# main.net
KiCad netlist of a schematic drawn in Altium Designer
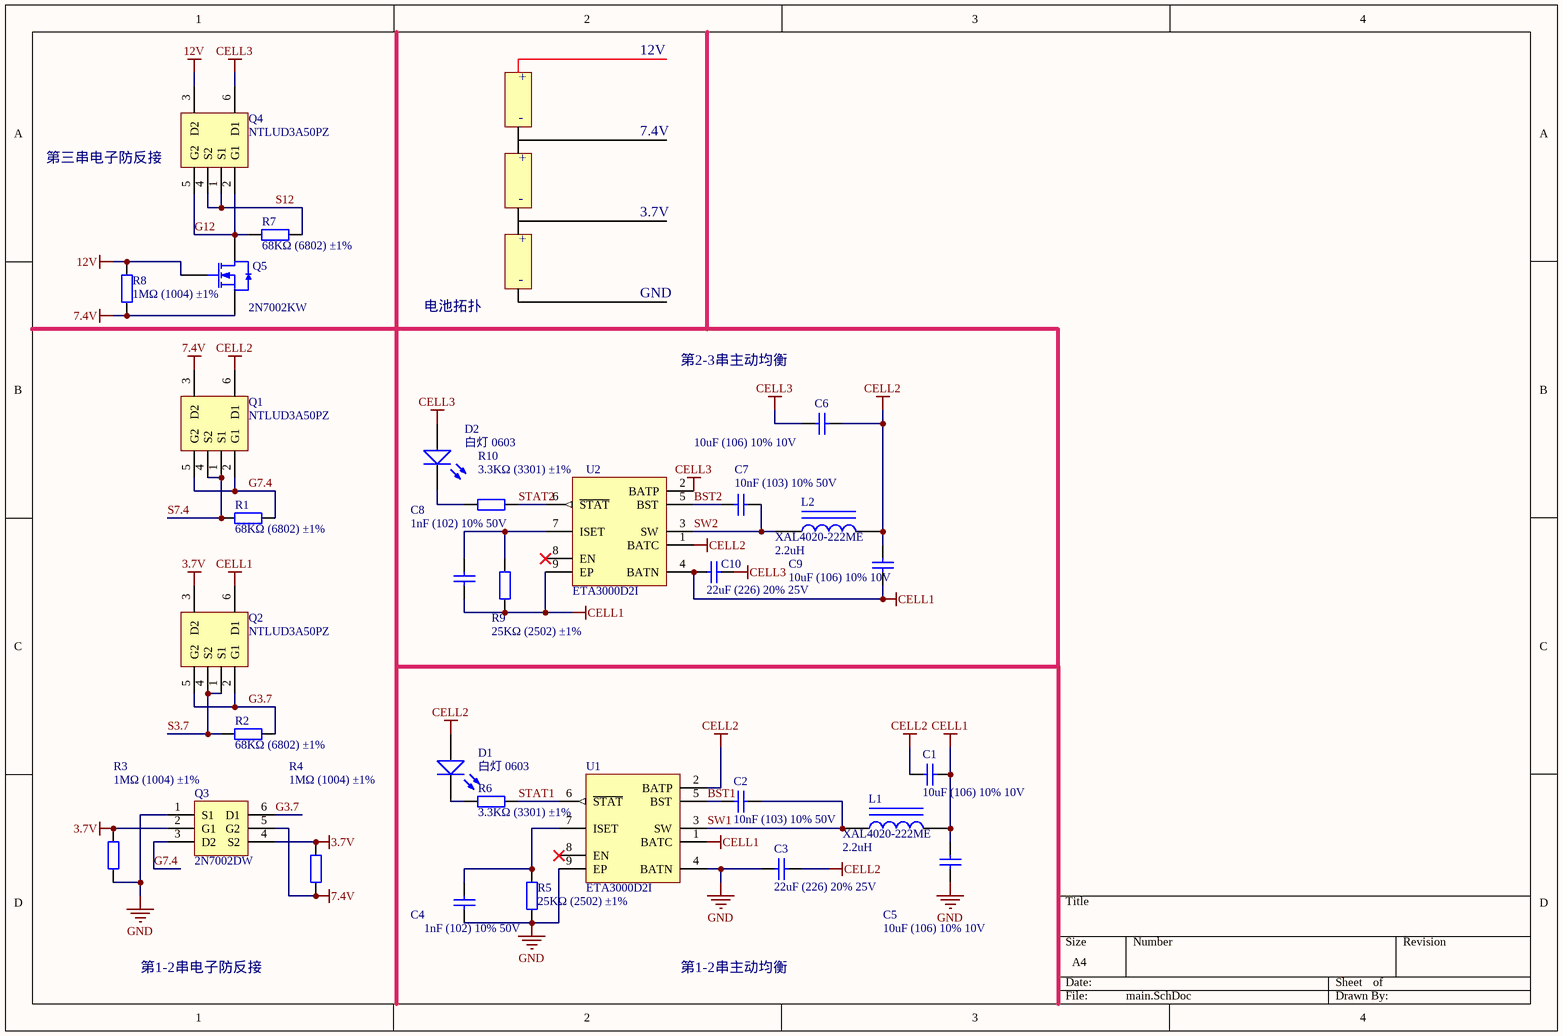
[diagram p0: main.SchDoc]

(export (version "E")
  (design (tool "Eeschema 10.0.6"))
  (components
    (comp (ref "C1")
      (value "10uF (106) 10% 10V")
      (footprint "0603_C")
      (description "贴片电容")
      (libsource (lib "Miscellaneous Devices LC") (part "0603 10uF (106) 10% 10V"))
    )
    (comp (ref "C2")
      (value "10nF (103) 10% 50V")
      (footprint "0402_C")
      (description "贴片电容")
      (libsource (lib "Miscellaneous Devices LC") (part "0402 10nF (103) 10% 50V"))
    )
    (comp (ref "C3")
      (value "22uF (226) 20% 25V")
      (footprint "0805_C")
      (description "贴片电容")
      (libsource (lib "Miscellaneous Devices LC") (part "0805 22uF (226) 20% 25V"))
    )
    (comp (ref "C4")
      (value "1nF (102) 10% 50V")
      (footprint "0402_C")
      (description "贴片电容")
      (libsource (lib "Miscellaneous Devices LC") (part "0402 1nF (102) 10% 50V"))
    )
    (comp (ref "C5")
      (value "10uF (106) 10% 10V")
      (footprint "0603_C")
      (description "贴片电容")
      (libsource (lib "Miscellaneous Devices LC") (part "0603 10uF (106) 10% 10V"))
    )
    (comp (ref "C6")
      (value "10uF (106) 10% 10V")
      (footprint "0603_C")
      (description "贴片电容")
      (libsource (lib "Miscellaneous Devices LC") (part "0603 10uF (106) 10% 10V"))
    )
    (comp (ref "C7")
      (value "10nF (103) 10% 50V")
      (footprint "0402_C")
      (description "贴片电容")
      (libsource (lib "Miscellaneous Devices LC") (part "0402 10nF (103) 10% 50V"))
    )
    (comp (ref "C8")
      (value "1nF (102) 10% 50V")
      (footprint "0402_C")
      (description "贴片电容")
      (libsource (lib "Miscellaneous Devices LC") (part "0402 1nF (102) 10% 50V"))
    )
    (comp (ref "C9")
      (value "10uF (106) 10% 10V")
      (footprint "0603_C")
      (description "贴片电容")
      (libsource (lib "Miscellaneous Devices LC") (part "0603 10uF (106) 10% 10V"))
    )
    (comp (ref "C10")
      (value "22uF (226) 20% 25V")
      (footprint "0805_C")
      (description "贴片电容")
      (libsource (lib "Miscellaneous Devices LC") (part "0805 22uF (226) 20% 25V"))
    )
    (comp (ref "D1")
      (value "白灯 0603")
      (footprint "0603_LED_S1")
      (description "发光二极管")
      (libsource (lib "Miscellaneous Devices LC") (part "0603 白灯"))
    )
    (comp (ref "D2")
      (value "白灯 0603")
      (footprint "0603_LED_S1")
      (description "发光二极管")
      (libsource (lib "Miscellaneous Devices LC") (part "0603 白灯"))
    )
    (comp (ref "L1")
      (value "XAL4020-222ME")
      (footprint "XAL4020-xxxME")
      (description "Coilcraft XAL4020 Series")
      (fields (field (name "ALTIUM_VALUE") "2.2uH") (field (name "PUBLISHER") "Altium Limited"))
      (libsource (lib "Miscellaneous Devices") (part "Inductor Iron"))
    )
    (comp (ref "L2")
      (value "XAL4020-222ME")
      (footprint "XAL4020-xxxME")
      (description "Coilcraft XAL4020 Series")
      (fields (field (name "ALTIUM_VALUE") "2.2uH") (field (name "PUBLISHER") "Altium Limited"))
      (libsource (lib "Miscellaneous Devices") (part "Inductor Iron"))
    )
    (comp (ref "Q1")
      (value "NTLUD3A50PZ")
      (footprint "UDFN-6_L2.0-W2.0-P0.65-BL_NTLUD3A50PZ")
      (description "Dual Symmetric P-MOS -20V -5.6A")
      (libsource (lib "custom") (part "NTLUD3A50PZ"))
    )
    (comp (ref "Q2")
      (value "NTLUD3A50PZ")
      (footprint "UDFN-6_L2.0-W2.0-P0.65-BL_NTLUD3A50PZ")
      (description "Dual Symmetric P-MOS -20V -5.6A")
      (libsource (lib "custom") (part "NTLUD3A50PZ"))
    )
    (comp (ref "Q3")
      (value "2N7002DW")
      (footprint "SC70-6")
      (description "Dual N-Channel MOSFET 60V340mA SOT-363")
      (libsource (lib "custom") (part "2N7002DW"))
    )
    (comp (ref "Q4")
      (value "NTLUD3A50PZ")
      (footprint "UDFN-6_L2.0-W2.0-P0.65-BL_NTLUD3A50PZ")
      (description "Dual Symmetric P-MOS -20V -5.6A")
      (libsource (lib "custom") (part "NTLUD3A50PZ"))
    )
    (comp (ref "Q5")
      (value "2N7002KW")
      (footprint "SC70-3")
      (description "MOS(场效应管)")
      (libsource (lib "Miscellaneous Devices LC") (part "2N7002 7002"))
    )
    (comp (ref "R1")
      (value "68KΩ (6802) ±1%")
      (footprint "0402_R")
      (description "贴片电阻")
      (libsource (lib "Miscellaneous Devices LC") (part "0402 68KΩ (6802) 1%"))
    )
    (comp (ref "R2")
      (value "68KΩ (6802) ±1%")
      (footprint "0402_R")
      (description "贴片电阻")
      (libsource (lib "Miscellaneous Devices LC") (part "0402 68KΩ (6802) 1%"))
    )
    (comp (ref "R3")
      (value "1MΩ (1004) ±1%")
      (footprint "0402_R")
      (description "贴片电阻")
      (libsource (lib "Miscellaneous Devices LC") (part "0402 1MΩ (1004) 1%"))
    )
    (comp (ref "R4")
      (value "1MΩ (1004) ±1%")
      (footprint "0402_R")
      (description "贴片电阻")
      (libsource (lib "Miscellaneous Devices LC") (part "0402 1MΩ (1004) 1%"))
    )
    (comp (ref "R5")
      (value "25KΩ (2502) ±1%")
      (footprint "0402_R")
      (description "贴片电阻")
      (libsource (lib "Miscellaneous Devices LC") (part "0402 20KΩ (2002) 1%"))
    )
    (comp (ref "R6")
      (value "3.3KΩ (3301) ±1%")
      (footprint "0402_R")
      (description "贴片电阻")
      (libsource (lib "Miscellaneous Devices LC") (part "0402 3.3KΩ (3301) 1%"))
    )
    (comp (ref "R7")
      (value "68KΩ (6802) ±1%")
      (footprint "0402_R")
      (description "贴片电阻")
      (libsource (lib "Miscellaneous Devices LC") (part "0402 68KΩ (6802) 1%"))
    )
    (comp (ref "R8")
      (value "1MΩ (1004) ±1%")
      (footprint "0402_R")
      (description "贴片电阻")
      (libsource (lib "Miscellaneous Devices LC") (part "0402 1MΩ (1004) 1%"))
    )
    (comp (ref "R9")
      (value "25KΩ (2502) ±1%")
      (footprint "0402_R")
      (description "贴片电阻")
      (libsource (lib "Miscellaneous Devices LC") (part "0402 20KΩ (2002) 1%"))
    )
    (comp (ref "R10")
      (value "3.3KΩ (3301) ±1%")
      (footprint "0402_R")
      (description "贴片电阻")
      (libsource (lib "Miscellaneous Devices LC") (part "0402 3.3KΩ (3301) 1%"))
    )
    (comp (ref "U1")
      (value "ETA3000D2I")
      (footprint "DFN2x2-8L")
      (description "2串锂电池电感主动均衡芯片,DFN2*2封装 2A均衡电流")
      (libsource (lib "custom") (part "ETA3000D2I"))
    )
    (comp (ref "U2")
      (value "ETA3000D2I")
      (footprint "DFN2x2-8L")
      (description "2串锂电池电感主动均衡芯片,DFN2*2封装 2A均衡电流")
      (libsource (lib "custom") (part "ETA3000D2I"))
    )
  )
  (nets
    (net (code "1") (name "/BST1") (class "Default")
      (node (ref "C2") (pin "2") (pinfunction "2_2") (pintype "passive"))
      (node (ref "U1") (pin "5") (pinfunction "BST_5") (pintype "power_in"))
    )
    (net (code "2") (name "/BST2") (class "Default")
      (node (ref "C7") (pin "1") (pinfunction "1_1") (pintype "passive"))
      (node (ref "U2") (pin "5") (pinfunction "BST_5") (pintype "power_in"))
    )
    (net (code "3") (name "/G3.7") (class "Default")
      (node (ref "Q2") (pin "2") (pinfunction "G1_2") (pintype "passive"))
      (node (ref "Q2") (pin "5") (pinfunction "G2_5") (pintype "passive"))
      (node (ref "Q3") (pin "6") (pinfunction "D1_6") (pintype "passive"))
      (node (ref "R2") (pin "2") (pinfunction "2_2") (pintype "passive"))
    )
    (net (code "4") (name "/G7.4") (class "Default")
      (node (ref "Q1") (pin "2") (pinfunction "G1_2") (pintype "passive"))
      (node (ref "Q1") (pin "5") (pinfunction "G2_5") (pintype "passive"))
      (node (ref "Q3") (pin "3") (pinfunction "D2_3") (pintype "passive"))
      (node (ref "R1") (pin "2") (pinfunction "2_2") (pintype "passive"))
    )
    (net (code "5") (name "/G12") (class "Default")
      (node (ref "Q4") (pin "2") (pinfunction "G1_2") (pintype "passive"))
      (node (ref "Q4") (pin "5") (pinfunction "G2_5") (pintype "passive"))
      (node (ref "Q5") (pin "3") (pinfunction "D_3") (pintype "passive"))
      (node (ref "R7") (pin "1") (pinfunction "1_1") (pintype "passive"))
    )
    (net (code "6") (name "/S3.7") (class "Default")
      (node (ref "Q2") (pin "1") (pinfunction "S1_1") (pintype "passive"))
      (node (ref "Q2") (pin "4") (pinfunction "S2_4") (pintype "passive"))
      (node (ref "R2") (pin "1") (pinfunction "1_1") (pintype "passive"))
    )
    (net (code "7") (name "/S7.4") (class "Default")
      (node (ref "Q1") (pin "1") (pinfunction "S1_1") (pintype "passive"))
      (node (ref "Q1") (pin "4") (pinfunction "S2_4") (pintype "passive"))
      (node (ref "R1") (pin "1") (pinfunction "1_1") (pintype "passive"))
    )
    (net (code "8") (name "/S12") (class "Default")
      (node (ref "Q4") (pin "1") (pinfunction "S1_1") (pintype "passive"))
      (node (ref "Q4") (pin "4") (pinfunction "S2_4") (pintype "passive"))
      (node (ref "R7") (pin "2") (pinfunction "2_2") (pintype "passive"))
    )
    (net (code "9") (name "/STAT1") (class "Default")
      (node (ref "R6") (pin "2") (pinfunction "2_2") (pintype "passive"))
      (node (ref "U1") (pin "6") (pinfunction "~{STAT}_6") (pintype "output"))
    )
    (net (code "10") (name "/STAT2") (class "Default")
      (node (ref "R10") (pin "2") (pinfunction "2_2") (pintype "passive"))
      (node (ref "U2") (pin "6") (pinfunction "~{STAT}_6") (pintype "output"))
    )
    (net (code "11") (name "/SW1") (class "Default")
      (node (ref "C2") (pin "1") (pinfunction "1_1") (pintype "passive"))
      (node (ref "L1") (pin "1") (pinfunction "1_1") (pintype "passive"))
      (node (ref "U1") (pin "3") (pinfunction "SW_3") (pintype "power_in"))
    )
    (net (code "12") (name "/SW2") (class "Default")
      (node (ref "C7") (pin "2") (pinfunction "2_2") (pintype "passive"))
      (node (ref "L2") (pin "1") (pinfunction "1_1") (pintype "passive"))
      (node (ref "U2") (pin "3") (pinfunction "SW_3") (pintype "power_in"))
    )
    (net (code "13") (name "3.7V") (class "Default")
      (node (ref "Q2") (pin "3") (pinfunction "D2_3") (pintype "passive"))
      (node (ref "Q3") (pin "2") (pinfunction "G1_2") (pintype "passive"))
      (node (ref "Q3") (pin "4") (pinfunction "S2_4") (pintype "passive"))
      (node (ref "R3") (pin "2") (pinfunction "2_2") (pintype "passive"))
      (node (ref "R4") (pin "2") (pinfunction "2_2") (pintype "passive"))
    )
    (net (code "14") (name "7.4V") (class "Default")
      (node (ref "Q1") (pin "3") (pinfunction "D2_3") (pintype "passive"))
      (node (ref "Q3") (pin "5") (pinfunction "G2_5") (pintype "passive"))
      (node (ref "Q5") (pin "2") (pinfunction "S_2") (pintype "passive"))
      (node (ref "R4") (pin "1") (pinfunction "1_1") (pintype "passive"))
      (node (ref "R8") (pin "1") (pinfunction "1_1") (pintype "passive"))
    )
    (net (code "15") (name "12V") (class "Default")
      (node (ref "Q4") (pin "3") (pinfunction "D2_3") (pintype "passive"))
      (node (ref "Q5") (pin "1") (pinfunction "G_1") (pintype "passive"))
      (node (ref "R8") (pin "2") (pinfunction "2_2") (pintype "passive"))
    )
    (net (code "16") (name "CELL1") (class "Default")
      (node (ref "C1") (pin "2") (pinfunction "2_2") (pintype "passive"))
      (node (ref "C10") (pin "1") (pinfunction "1_1") (pintype "passive"))
      (node (ref "C5") (pin "2") (pinfunction "2_2") (pintype "passive"))
      (node (ref "C8") (pin "1") (pinfunction "1_1") (pintype "passive"))
      (node (ref "C9") (pin "1") (pinfunction "1_1") (pintype "passive"))
      (node (ref "L1") (pin "2") (pinfunction "2_2") (pintype "passive"))
      (node (ref "Q2") (pin "6") (pinfunction "D1_6") (pintype "passive"))
      (node (ref "R9") (pin "1") (pinfunction "1_1") (pintype "passive"))
      (node (ref "U1") (pin "1") (pinfunction "BATC_1") (pintype "power_in"))
      (node (ref "U2") (pin "4") (pinfunction "BATN_4") (pintype "power_in"))
      (node (ref "U2") (pin "9") (pinfunction "EP_9") (pintype "passive"))
    )
    (net (code "17") (name "CELL2") (class "Default")
      (node (ref "C1") (pin "1") (pinfunction "1_1") (pintype "passive"))
      (node (ref "C3") (pin "2") (pinfunction "2_2") (pintype "passive"))
      (node (ref "C6") (pin "2") (pinfunction "2_2") (pintype "passive"))
      (node (ref "C9") (pin "2") (pinfunction "2_2") (pintype "passive"))
      (node (ref "D1") (pin "A") (pinfunction "A_A") (pintype "passive"))
      (node (ref "L2") (pin "2") (pinfunction "2_2") (pintype "passive"))
      (node (ref "Q1") (pin "6") (pinfunction "D1_6") (pintype "passive"))
      (node (ref "U1") (pin "2") (pinfunction "BATP_2") (pintype "power_in"))
      (node (ref "U2") (pin "1") (pinfunction "BATC_1") (pintype "power_in"))
    )
    (net (code "18") (name "CELL3") (class "Default")
      (node (ref "C10") (pin "2") (pinfunction "2_2") (pintype "passive"))
      (node (ref "C6") (pin "1") (pinfunction "1_1") (pintype "passive"))
      (node (ref "D2") (pin "A") (pinfunction "A_A") (pintype "passive"))
      (node (ref "Q4") (pin "6") (pinfunction "D1_6") (pintype "passive"))
      (node (ref "U2") (pin "2") (pinfunction "BATP_2") (pintype "power_in"))
    )
    (net (code "19") (name "GND") (class "Default")
      (node (ref "C3") (pin "1") (pinfunction "1_1") (pintype "passive"))
      (node (ref "C4") (pin "1") (pinfunction "1_1") (pintype "passive"))
      (node (ref "C5") (pin "1") (pinfunction "1_1") (pintype "passive"))
      (node (ref "Q3") (pin "1") (pinfunction "S1_1") (pintype "passive"))
      (node (ref "R3") (pin "1") (pinfunction "1_1") (pintype "passive"))
      (node (ref "R5") (pin "1") (pinfunction "1_1") (pintype "passive"))
      (node (ref "U1") (pin "4") (pinfunction "BATN_4") (pintype "power_in"))
      (node (ref "U1") (pin "9") (pinfunction "EP_9") (pintype "passive"))
    )
    (net (code "20") (name "Net-(D1-PadK)") (class "Default")
      (node (ref "D1") (pin "K") (pinfunction "K_K") (pintype "passive"))
      (node (ref "R6") (pin "1") (pinfunction "1_1") (pintype "passive"))
    )
    (net (code "21") (name "Net-(D2-PadK)") (class "Default")
      (node (ref "D2") (pin "K") (pinfunction "K_K") (pintype "passive"))
      (node (ref "R10") (pin "1") (pinfunction "1_1") (pintype "passive"))
    )
    (net (code "22") (name "Net-(U1-ISET)") (class "Default")
      (node (ref "C4") (pin "2") (pinfunction "2_2") (pintype "passive"))
      (node (ref "R5") (pin "2") (pinfunction "2_2") (pintype "passive"))
      (node (ref "U1") (pin "7") (pinfunction "ISET_7") (pintype "passive"))
    )
    (net (code "23") (name "Net-(U2-ISET)") (class "Default")
      (node (ref "C8") (pin "2") (pinfunction "2_2") (pintype "passive"))
      (node (ref "R9") (pin "2") (pinfunction "2_2") (pintype "passive"))
      (node (ref "U2") (pin "7") (pinfunction "ISET_7") (pintype "passive"))
    )
    (net (code "24") (name "unconnected-(U1-EN-Pad8)") (class "Default")
      (node (ref "U1") (pin "8") (pinfunction "EN_8") (pintype "passive+no_connect"))
    )
    (net (code "25") (name "unconnected-(U2-EN-Pad8)") (class "Default")
      (node (ref "U2") (pin "8") (pinfunction "EN_8") (pintype "passive+no_connect"))
    )
  )
)
